# STM32_microcontroller_IOs.net
KiCad netlist of a schematic drawn in Altium Designer
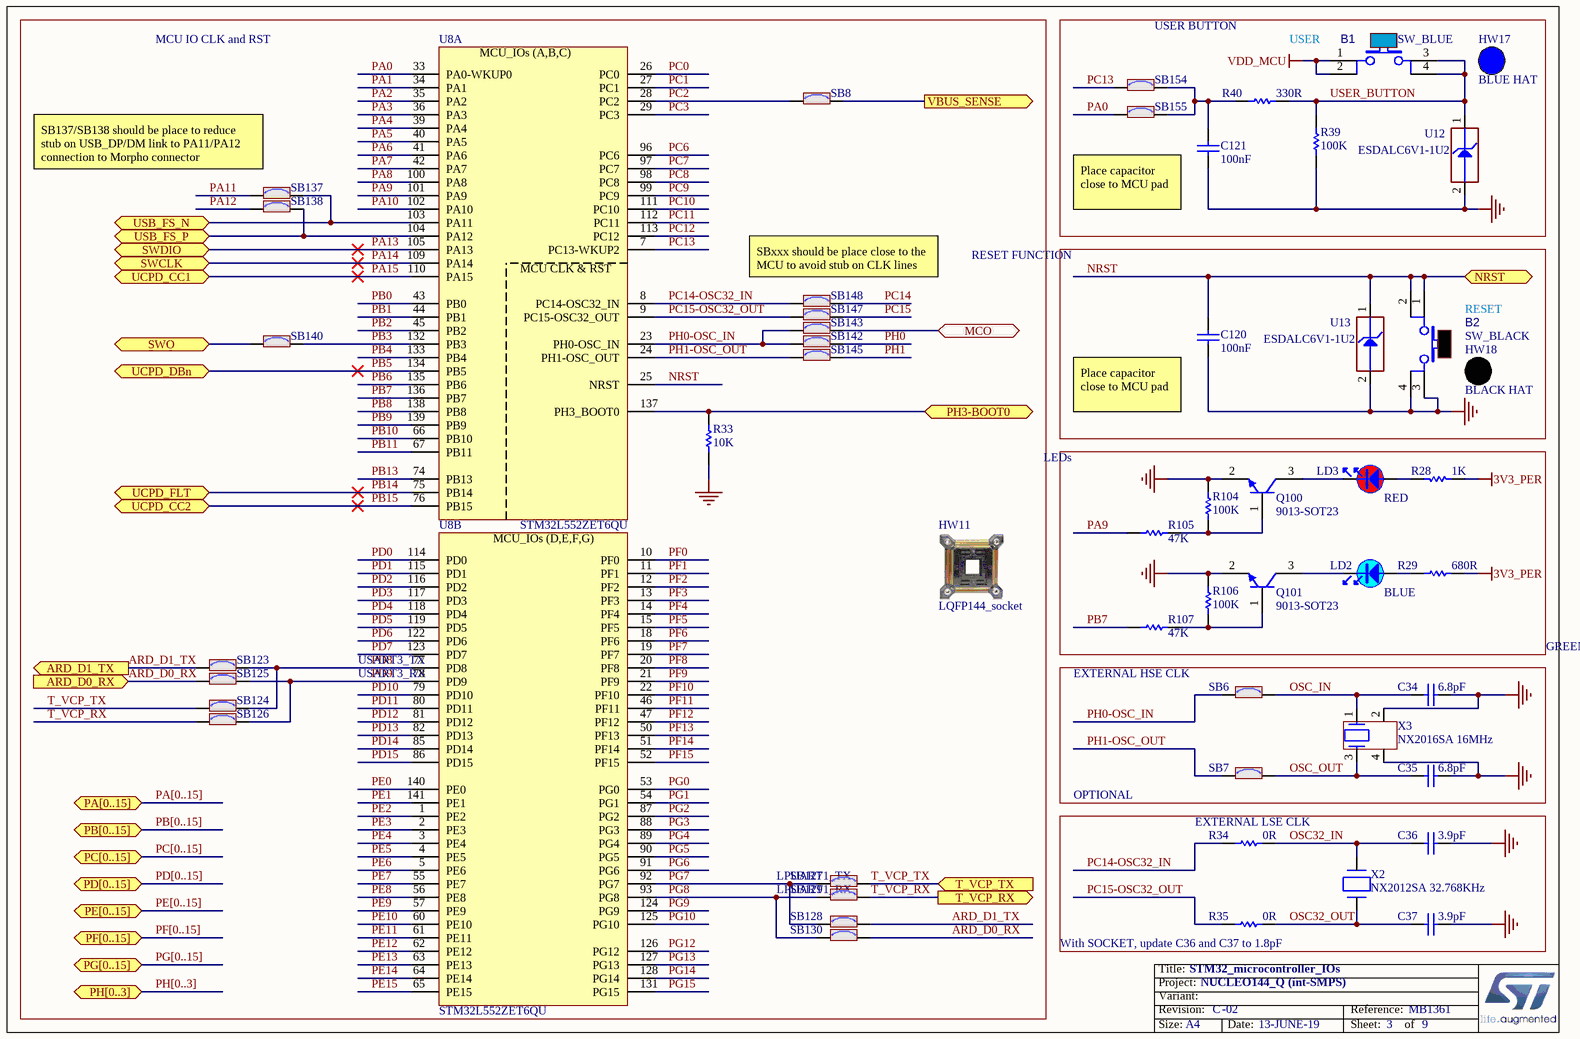
[diagram p0: STM32_microcontroller_IOs.SchDoc]

(export (version "E")
  (design (tool "Eeschema 10.0.6"))
  (components
    (comp (ref "B1")
      (value "SW_BLUE")
      (footprint "SWI_WEALTHMETAL_TD-0341_4P_BLUE")
      (description "Non-Open Push-Button 0.1A 24V BLUE")
      (fields
        (field (name "INTERNAL_PART_NUMBER") "MCD-00002")
        (field (name "MANUFACTURER_PART_NUMBER") "TD0341X-G01-BLU")
        (field (name "PROVIDED_BY") "Subcon")
      )
      (libsource (lib "MCD_PARTS_database") (part "SW-PUSH-CMS_BLUE"))
    )
    (comp (ref "B2")
      (value "SW_BLACK")
      (footprint "SWI_WEALTHMETAL_TD-0341_4P_BLACK")
      (description "Non-Open Push-Button 0.1A 24V BLACK")
      (fields
        (field (name "INTERNAL_PART_NUMBER") "MCD-00001")
        (field (name "MANUFACTURER_PART_NUMBER") "TD0341X-G01-BLA")
        (field (name "PROVIDED_BY") "Subcon")
      )
      (libsource (lib "MCD_PARTS_database") (part "SW-PUSH-CMS_BLACK"))
    )
    (comp (ref "C34")
      (value "6.8pF")
      (footprint "C0402")
      (description "Capacitor, MLCC, 6.8pF, 50V, NPO, +-0.25pF, 0402, T=0.5mm")
      (fields
        (field (name "INTERNAL_PART_NUMBER") "MCD-00674")
        (field (name "MANUFACTURER_PART_NUMBER") "CC0402CRNPO9BN6R8")
        (field (name "PROVIDED_BY") "Subcon")
      )
      (libsource (lib "MCD_PARTS_database") (part "Capacitor"))
    )
    (comp (ref "C35")
      (value "6.8pF")
      (footprint "C0402")
      (description "Capacitor, MLCC, 6.8pF, 50V, NPO, +-0.25pF, 0402, T=0.5mm")
      (fields
        (field (name "INTERNAL_PART_NUMBER") "MCD-00674")
        (field (name "MANUFACTURER_PART_NUMBER") "CC0402CRNPO9BN6R8")
        (field (name "PROVIDED_BY") "Subcon")
      )
      (libsource (lib "MCD_PARTS_database") (part "Capacitor"))
    )
    (comp (ref "C36")
      (value "3.9pF")
      (footprint "C0402")
      (description "Capacitor, MLCC, 3.9pF, 50V, NPO, +-0.25pF, 0402, T=0,5mm")
      (fields
        (field (name "INTERNAL_PART_NUMBER") "MCD-00556")
        (field (name "MANUFACTURER_PART_NUMBER") "CC0402CRNPO9BN3R9")
        (field (name "PROVIDED_BY") "SUBCO")
      )
      (libsource (lib "MCD_PARTS_database") (part "Capacitor"))
    )
    (comp (ref "C37")
      (value "3.9pF")
      (footprint "C0402")
      (description "Capacitor, MLCC, 3.9pF, 50V, NPO, +-0.25pF, 0402, T=0,5mm")
      (fields
        (field (name "INTERNAL_PART_NUMBER") "MCD-00556")
        (field (name "MANUFACTURER_PART_NUMBER") "CC0402CRNPO9BN3R9")
        (field (name "PROVIDED_BY") "SUBCO")
      )
      (libsource (lib "MCD_PARTS_database") (part "Capacitor"))
    )
    (comp (ref "C120")
      (value "100nF")
      (footprint "C0603")
      (description "Capacitor, MLCC, 100nF, 16V, X7R, 10%, 0603, T=0,8mm")
      (fields
        (field (name "INTERNAL_PART_NUMBER") "MCD-00211")
        (field (name "MANUFACTURER_PART_NUMBER") "CC0603KRX7R7BB104")
        (field (name "PROVIDED_BY") "Subcon")
      )
      (libsource (lib "MCD_PARTS_database") (part "Capacitor"))
    )
    (comp (ref "C121")
      (value "100nF")
      (footprint "C0603")
      (description "Capacitor, MLCC, 100nF, 16V, X7R, 10%, 0603, T=0,8mm")
      (fields
        (field (name "INTERNAL_PART_NUMBER") "MCD-00211")
        (field (name "MANUFACTURER_PART_NUMBER") "CC0603KRX7R7BB104")
        (field (name "PROVIDED_BY") "Subcon")
      )
      (libsource (lib "MCD_PARTS_database") (part "Capacitor"))
    )
    (comp (ref "HW11")
      (value "LQFP144_socket")
      (description "Yamaichi socket for LQFP144, with positioning pins.")
      (fields
        (field (name "INTERNAL_PART_NUMBER") "MCD-01015")
        (field (name "MANUFACTURER_PART_NUMBER") "IC149-144-145-B5")
        (field (name "PROVIDED_BY") "Subcon")
      )
      (libsource (lib "MCD_PARTS_database") (part "SOCKET_LQFP144"))
    )
    (comp (ref "HW17")
      (value "BLUE HAT")
      (description "Blue Hat for switch TD0341X-G01-BLU")
      (fields
        (field (name "INTERNAL_PART_NUMBER") "MCD-00634")
        (field (name "MANUFACTURER_PART_NUMBER") "988.16.09.3.00002_SH-517")
        (field (name "PROVIDED_BY") "Subcon")
      )
      (libsource (lib "MCD_PARTS_database") (part "BUTTON_HAT_BLUE"))
    )
    (comp (ref "HW18")
      (value "BLACK HAT")
      (description "Black Hat for switch TD0341X-G01-BLA")
      (fields
        (field (name "INTERNAL_PART_NUMBER") "MCD-00635")
        (field (name "MANUFACTURER_PART_NUMBER") "988.16.09.3.00003_SH-517")
        (field (name "PROVIDED_BY") "Subcon")
      )
      (libsource (lib "MCD_PARTS_database") (part "BUTTON_HAT_BLACK"))
    )
    (comp (ref "LD2")
      (value "BLUE")
      (footprint "LED_0603_VISHAY_VLMB1300-GS08_BLUE_1A2K_H0P8")
      (description "LED Blue, 0603 SMD, 3.3 V Forward Voltage")
      (fields
        (field (name "INTERNAL_PART_NUMBER") "MCD-00584")
        (field (name "MANUFACTURER_PART_NUMBER") "VLMB1300-GS08")
        (field (name "PROVIDED_BY") "Subcon")
      )
      (libsource (lib "MCD_PARTS_database") (part "LED_blue"))
    )
    (comp (ref "LD3")
      (value "RED")
      (footprint "LED_0603_RED_H0P4")
      (description "LED, Red, 0603")
      (fields
        (field (name "INTERNAL_PART_NUMBER") "MCD-00322")
        (field (name "MANUFACTURER_PART_NUMBER") "19-217/R6C-AL1M2VY/3T")
        (field (name "PROVIDED_BY") "Subcon")
      )
      (libsource (lib "MCD_PARTS_database") (part "LED_red"))
    )
    (comp (ref "Q100")
      (value "9013-SOT23")
      (footprint "NPN_SOT23")
      (description "NPN Bipolar Transistor")
      (fields
        (field (name "INTERNAL_PART_NUMBER") "MCD-00073")
        (field (name "MANUFACTURER_PART_NUMBER") "BSR14")
        (field (name "PROVIDED_BY") "Subcon")
      )
      (libsource (lib "MCD_PARTS_database") (part "9013-SOT23"))
    )
    (comp (ref "Q101")
      (value "9013-SOT23")
      (footprint "NPN_SOT23")
      (description "NPN Bipolar Transistor")
      (fields
        (field (name "INTERNAL_PART_NUMBER") "MCD-00073")
        (field (name "MANUFACTURER_PART_NUMBER") "BSR14")
        (field (name "PROVIDED_BY") "Subcon")
      )
      (libsource (lib "MCD_PARTS_database") (part "9013-SOT23"))
    )
    (comp (ref "R28")
      (value "1K")
      (footprint "R0603")
      (description "Resistor,1K,0603,1%,1/10W")
      (fields
        (field (name "INTERNAL_PART_NUMBER") "MCD-00070")
        (field (name "MANUFACTURER_PART_NUMBER") "RC0603FR-071KL")
        (field (name "PROVIDED_BY") "Subcon")
      )
      (libsource (lib "MCD_PARTS_database") (part "Resistor"))
    )
    (comp (ref "R29")
      (value "680R")
      (footprint "R0603")
      (description "Resistor,680R,0603,1%,1/10W")
      (fields
        (field (name "INTERNAL_PART_NUMBER") "MCD-00508")
        (field (name "MANUFACTURER_PART_NUMBER") "RC0603FR-07680RL")
        (field (name "PROVIDED_BY") "Subcon")
      )
      (libsource (lib "MCD_PARTS_database") (part "Resistor"))
    )
    (comp (ref "R33")
      (value "10K")
      (footprint "R0603")
      (description "Resistor,10K,0603,1%,1/10W")
      (fields
        (field (name "INTERNAL_PART_NUMBER") "MCD-00220")
        (field (name "MANUFACTURER_PART_NUMBER") "RC0603FR-0710KL")
        (field (name "PROVIDED_BY") "Subcon")
      )
      (libsource (lib "MCD_PARTS_database") (part "Resistor"))
    )
    (comp (ref "R34")
      (value "0R")
      (footprint "R0603")
      (description "Resistor,0R,0603,5%,1/10W")
      (fields
        (field (name "INTERNAL_PART_NUMBER") "MCD-00056")
        (field (name "MANUFACTURER_PART_NUMBER") "RC0603JR-070RL")
        (field (name "PROVIDED_BY") "subcon")
      )
      (libsource (lib "MCD_PARTS_database") (part "Resistor"))
    )
    (comp (ref "R35")
      (value "0R")
      (footprint "R0603")
      (description "Resistor,0R,0603,5%,1/10W")
      (fields
        (field (name "INTERNAL_PART_NUMBER") "MCD-00056")
        (field (name "MANUFACTURER_PART_NUMBER") "RC0603JR-070RL")
        (field (name "PROVIDED_BY") "subcon")
      )
      (libsource (lib "MCD_PARTS_database") (part "Resistor"))
    )
    (comp (ref "R39")
      (value "100K")
      (footprint "R0603")
      (description "Resistor,100K,0603,1%,1/10W")
      (fields
        (field (name "INTERNAL_PART_NUMBER") "MCD-00223")
        (field (name "MANUFACTURER_PART_NUMBER") "RC0603FR-07100KL")
        (field (name "PROVIDED_BY") "Subcon")
      )
      (libsource (lib "MCD_PARTS_database") (part "Resistor"))
    )
    (comp (ref "R40")
      (value "330R")
      (footprint "R0603")
      (description "Resistor,330R,0603,1%,1/10W")
      (fields
        (field (name "INTERNAL_PART_NUMBER") "MCD-00197")
        (field (name "MANUFACTURER_PART_NUMBER") "RC0603FR-07330RL")
        (field (name "PROVIDED_BY") "Subcon")
      )
      (libsource (lib "MCD_PARTS_database") (part "Resistor"))
    )
    (comp (ref "R104")
      (value "100K")
      (footprint "R0603")
      (description "Resistor,100K,0603,1%,1/10W")
      (fields
        (field (name "INTERNAL_PART_NUMBER") "MCD-00223")
        (field (name "MANUFACTURER_PART_NUMBER") "RC0603FR-07100KL")
        (field (name "PROVIDED_BY") "Subcon")
      )
      (libsource (lib "MCD_PARTS_database") (part "Resistor"))
    )
    (comp (ref "R105")
      (value "47K")
      (footprint "R0603")
      (description "Resistor,47K,0603,1%,1/10W")
      (fields
        (field (name "INTERNAL_PART_NUMBER") "MCD-00222")
        (field (name "MANUFACTURER_PART_NUMBER") "RC0603FR-0747KL")
        (field (name "PROVIDED_BY") "Subcon")
      )
      (libsource (lib "MCD_PARTS_database") (part "Resistor"))
    )
    (comp (ref "R106")
      (value "100K")
      (footprint "R0603")
      (description "Resistor,100K,0603,1%,1/10W")
      (fields
        (field (name "INTERNAL_PART_NUMBER") "MCD-00223")
        (field (name "MANUFACTURER_PART_NUMBER") "RC0603FR-07100KL")
        (field (name "PROVIDED_BY") "Subcon")
      )
      (libsource (lib "MCD_PARTS_database") (part "Resistor"))
    )
    (comp (ref "R107")
      (value "47K")
      (footprint "R0603")
      (description "Resistor,47K,0603,1%,1/10W")
      (fields
        (field (name "INTERNAL_PART_NUMBER") "MCD-00222")
        (field (name "MANUFACTURER_PART_NUMBER") "RC0603FR-0747KL")
        (field (name "PROVIDED_BY") "Subcon")
      )
      (libsource (lib "MCD_PARTS_database") (part "Resistor"))
    )
    (comp (ref "SB6")
      (value "~")
      (footprint "SOLDER-BRIDGE_R0603-0R")
      (description "Solder Bridge ON")
      (fields (field (name "INTERNAL_PART_NUMBER") "MCD-00071") (field (name "PROVIDED_BY") "Subcon"))
      (libsource (lib "MCD_PARTS_database") (part "SB_ON"))
    )
    (comp (ref "SB7")
      (value "~")
      (footprint "SOLDER-BRIDGE_R0603-0R")
      (description "Solder Bridge ON")
      (fields (field (name "INTERNAL_PART_NUMBER") "MCD-00071") (field (name "PROVIDED_BY") "Subcon"))
      (libsource (lib "MCD_PARTS_database") (part "SB_ON"))
    )
    (comp (ref "SB8")
      (value "~")
      (footprint "SOLDER-BRIDGE_R0603-0R")
      (description "Solder Bridge ON")
      (fields (field (name "INTERNAL_PART_NUMBER") "MCD-00071") (field (name "PROVIDED_BY") "Subcon"))
      (libsource (lib "MCD_PARTS_database") (part "SB_ON"))
    )
    (comp (ref "SB123")
      (value "~")
      (footprint "SOLDER-BRIDGE_R0603-0R")
      (description "Solder Bridge ON")
      (fields (field (name "INTERNAL_PART_NUMBER") "MCD-00071") (field (name "PROVIDED_BY") "Subcon"))
      (libsource (lib "") (part "SB_ON_1"))
    )
    (comp (ref "SB124")
      (value "~")
      (footprint "SOLDER-BRIDGE_R0603-0R")
      (description "Solder Bridge ON")
      (fields (field (name "INTERNAL_PART_NUMBER") "MCD-00071") (field (name "PROVIDED_BY") "Subcon"))
      (libsource (lib "") (part "SB_ON_1"))
    )
    (comp (ref "SB125")
      (value "~")
      (footprint "SOLDER-BRIDGE_R0603-0R")
      (description "Solder Bridge ON")
      (fields (field (name "INTERNAL_PART_NUMBER") "MCD-00071") (field (name "PROVIDED_BY") "Subcon"))
      (libsource (lib "") (part "SB_ON_1"))
    )
    (comp (ref "SB126")
      (value "~")
      (footprint "SOLDER-BRIDGE_R0603-0R")
      (description "Solder Bridge ON")
      (fields (field (name "INTERNAL_PART_NUMBER") "MCD-00071") (field (name "PROVIDED_BY") "Subcon"))
      (libsource (lib "") (part "SB_ON_1"))
    )
    (comp (ref "SB127")
      (value "~")
      (footprint "SOLDER-BRIDGE_R0603-0R")
      (description "Solder Bridge ON")
      (fields (field (name "INTERNAL_PART_NUMBER") "MCD-00071") (field (name "PROVIDED_BY") "Subcon"))
      (libsource (lib "") (part "SB_ON_1"))
    )
    (comp (ref "SB128")
      (value "~")
      (footprint "SOLDER-BRIDGE_R0603-0R")
      (description "Solder Bridge ON")
      (fields (field (name "INTERNAL_PART_NUMBER") "MCD-00071") (field (name "PROVIDED_BY") "Subcon"))
      (libsource (lib "") (part "SB_ON_1"))
    )
    (comp (ref "SB129")
      (value "~")
      (footprint "SOLDER-BRIDGE_R0603-0R")
      (description "Solder Bridge ON")
      (fields (field (name "INTERNAL_PART_NUMBER") "MCD-00071") (field (name "PROVIDED_BY") "Subcon"))
      (libsource (lib "") (part "SB_ON_1"))
    )
    (comp (ref "SB130")
      (value "~")
      (footprint "SOLDER-BRIDGE_R0603-0R")
      (description "Solder Bridge ON")
      (fields (field (name "INTERNAL_PART_NUMBER") "MCD-00071") (field (name "PROVIDED_BY") "Subcon"))
      (libsource (lib "") (part "SB_ON_1"))
    )
    (comp (ref "SB137")
      (value "~")
      (footprint "SOLDER-BRIDGE_R0603-0R")
      (description "Solder Bridge ON")
      (fields (field (name "INTERNAL_PART_NUMBER") "MCD-00071") (field (name "PROVIDED_BY") "Subcon"))
      (libsource (lib "MCD_PARTS_database") (part "SB_ON"))
    )
    (comp (ref "SB138")
      (value "~")
      (footprint "SOLDER-BRIDGE_R0603-0R")
      (description "Solder Bridge ON")
      (fields (field (name "INTERNAL_PART_NUMBER") "MCD-00071") (field (name "PROVIDED_BY") "Subcon"))
      (libsource (lib "MCD_PARTS_database") (part "SB_ON"))
    )
    (comp (ref "SB140")
      (value "~")
      (footprint "SOLDER-BRIDGE_R0603-0R")
      (description "Solder Bridge ON")
      (fields (field (name "INTERNAL_PART_NUMBER") "MCD-00071") (field (name "PROVIDED_BY") "Subcon"))
      (libsource (lib "MCD_PARTS_database") (part "SB_ON"))
    )
    (comp (ref "SB142")
      (value "~")
      (footprint "SOLDER-BRIDGE_R0603-0R")
      (description "Solder Bridge ON")
      (fields (field (name "INTERNAL_PART_NUMBER") "MCD-00071") (field (name "PROVIDED_BY") "Subcon"))
      (libsource (lib "MCD_PARTS_database") (part "SB_ON"))
    )
    (comp (ref "SB143")
      (value "~")
      (footprint "SOLDER-BRIDGE_R0603-0R")
      (description "Solder Bridge ON")
      (fields (field (name "INTERNAL_PART_NUMBER") "MCD-00071") (field (name "PROVIDED_BY") "Subcon"))
      (libsource (lib "MCD_PARTS_database") (part "SB_ON"))
    )
    (comp (ref "SB145")
      (value "~")
      (footprint "SOLDER-BRIDGE_R0603-0R")
      (description "Solder Bridge ON")
      (fields (field (name "INTERNAL_PART_NUMBER") "MCD-00071") (field (name "PROVIDED_BY") "Subcon"))
      (libsource (lib "MCD_PARTS_database") (part "SB_ON"))
    )
    (comp (ref "SB147")
      (value "~")
      (footprint "SOLDER-BRIDGE_R0603-0R")
      (description "Solder Bridge ON")
      (fields (field (name "INTERNAL_PART_NUMBER") "MCD-00071") (field (name "PROVIDED_BY") "Subcon"))
      (libsource (lib "MCD_PARTS_database") (part "SB_ON"))
    )
    (comp (ref "SB148")
      (value "~")
      (footprint "SOLDER-BRIDGE_R0603-0R")
      (description "Solder Bridge ON")
      (fields (field (name "INTERNAL_PART_NUMBER") "MCD-00071") (field (name "PROVIDED_BY") "Subcon"))
      (libsource (lib "MCD_PARTS_database") (part "SB_ON"))
    )
    (comp (ref "SB154")
      (value "~")
      (footprint "SOLDER-BRIDGE_R0603-0R")
      (description "Solder Bridge ON")
      (fields (field (name "INTERNAL_PART_NUMBER") "MCD-00071") (field (name "PROVIDED_BY") "Subcon"))
      (libsource (lib "") (part "SB_ON_1"))
    )
    (comp (ref "SB155")
      (value "~")
      (footprint "SOLDER-BRIDGE_R0603-0R")
      (description "Solder Bridge ON")
      (fields (field (name "INTERNAL_PART_NUMBER") "MCD-00071") (field (name "PROVIDED_BY") "Subcon"))
      (libsource (lib "") (part "SB_ON_1"))
    )
    (comp (ref "U8")
      (value "STM32L552ZET6QU")
      (footprint "ICC_LQFP144_20X20_P050")
      (description "STM32L552ZET6Q MCU,LQFP144 20x20, 0.5, no AES, Q for Int SMPS")
      (fields
        (field (name "INTERNAL_PART_NUMBER") "MCD-01055")
        (field (name "MANUFACTURER") "STMICROELECTRONICS")
        (field (name "PROVIDED_BY") "SUBCO with ST control")
      )
      (libsource (lib "MCD_PARTS_database") (part "STM32L552ZET6QU"))
    )
    (comp (ref "U12")
      (value "ESDALC6V1-1U2")
      (footprint "ESD_ST0201")
      (description "ESD protection 6V1")
      (fields
        (field (name "INTERNAL_PART_NUMBER") "MCD-00170")
        (field (name "MANUFACTURER") "STMICROELECTRONICS")
        (field (name "PROVIDED_BY") "Subcon")
      )
      (libsource (lib "MCD_PARTS_database") (part "ESD-TRANSIL"))
    )
    (comp (ref "U13")
      (value "ESDALC6V1-1U2")
      (footprint "ESD_ST0201")
      (description "ESD protection 6V1")
      (fields
        (field (name "INTERNAL_PART_NUMBER") "MCD-00170")
        (field (name "MANUFACTURER") "STMICROELECTRONICS")
        (field (name "PROVIDED_BY") "Subcon")
      )
      (libsource (lib "MCD_PARTS_database") (part "ESD-TRANSIL"))
    )
    (comp (ref "X2")
      (value "NX2012SA 32.768KHz")
      (footprint "CRY_NX2012SA_2P")
      (description "Crystal 32.768kHz, 6pF, -+20PPM, R=80K, SMD")
      (fields
        (field (name "INTERNAL_PART_NUMBER") "MCD-01479")
        (field (name "MANUFACTURER_PART_NUMBER") "NX2012SA 32.768KHz EXS00A-MU00527")
        (field (name "PROVIDED_BY") "SUBCO")
      )
      (libsource (lib "MCD_PARTS_database") (part "XTAL_2_PINS"))
    )
    (comp (ref "X3")
      (value "NX2016SA 16MHz")
      (footprint "CRY_NX2016SA_4P")
      (description "Crystal 16 MHz, 8pF, -+20 PPM, R=200Ω, SMD")
      (fields
        (field (name "INTERNAL_PART_NUMBER") "MCD-01476")
        (field (name "MANUFACTURER_PART_NUMBER") "NX2016SA 16 MHz EXS00A-CS07826")
      )
      (libsource (lib "MCD_PARTS_database") (part "XTAL_4_PINS"))
    )
  )
  (nets
    (net (code "7") (name "/ARD_D0_RX") (class "Default")
      (node (ref "SB125") (pin "2") (pinfunction "2_2") (pintype "passive"))
      (node (ref "SB130") (pin "1") (pinfunction "1_1") (pintype "passive"))
    )
    (net (code "8") (name "/ARD_D1_TX") (class "Default")
      (node (ref "SB123") (pin "2") (pinfunction "2_2") (pintype "passive"))
      (node (ref "SB128") (pin "1") (pinfunction "1_1") (pintype "passive"))
    )
    (net (code "9") (name "/MCO") (class "Default")
      (node (ref "SB143") (pin "2") (pinfunction "2_2") (pintype "passive"))
    )
    (net (code "10") (name "/NRST") (class "Default")
      (node (ref "B2") (pin "1") (pinfunction "1_1") (pintype "passive"))
      (node (ref "B2") (pin "2") (pinfunction "2_2") (pintype "passive"))
      (node (ref "C120") (pin "2") (pinfunction "2_2") (pintype "passive"))
      (node (ref "U13") (pin "1") (pinfunction "IO1_1") (pintype "passive"))
      (node (ref "U8") (pin "25") (pinfunction "NRST_25") (pintype "passive"))
    )
    (net (code "11") (name "/OSC32_IN") (class "Default")
      (node (ref "C36") (pin "1") (pinfunction "1_1") (pintype "passive"))
      (node (ref "R34") (pin "2") (pinfunction "2_2") (pintype "passive"))
      (node (ref "X2") (pin "2") (pinfunction "X2_2") (pintype "passive"))
    )
    (net (code "12") (name "/OSC32_OUT") (class "Default")
      (node (ref "C37") (pin "1") (pinfunction "1_1") (pintype "passive"))
      (node (ref "R35") (pin "2") (pinfunction "2_2") (pintype "passive"))
      (node (ref "X2") (pin "1") (pinfunction "X1_1") (pintype "passive"))
    )
    (net (code "13") (name "/OSC_IN") (class "Default")
      (node (ref "C34") (pin "1") (pinfunction "1_1") (pintype "passive"))
      (node (ref "SB6") (pin "2") (pinfunction "2_2") (pintype "passive"))
      (node (ref "X3") (pin "1") (pinfunction "1_1") (pintype "passive"))
    )
    (net (code "14") (name "/OSC_OUT") (class "Default")
      (node (ref "C35") (pin "1") (pinfunction "1_1") (pintype "passive"))
      (node (ref "SB7") (pin "2") (pinfunction "2_2") (pintype "passive"))
      (node (ref "X3") (pin "3") (pinfunction "3_3") (pintype "passive"))
    )
    (net (code "15") (name "/PA0") (class "Default")
      (node (ref "SB155") (pin "2") (pinfunction "2_2") (pintype "passive"))
      (node (ref "U8") (pin "33") (pinfunction "PA0-WKUP0_33") (pintype "passive"))
    )
    (net (code "16") (name "/PA1") (class "Default")
      (node (ref "U8") (pin "34") (pinfunction "PA1_34") (pintype "passive"))
    )
    (net (code "17") (name "/PA2") (class "Default")
      (node (ref "U8") (pin "35") (pinfunction "PA2_35") (pintype "passive"))
    )
    (net (code "18") (name "/PA3") (class "Default")
      (node (ref "U8") (pin "36") (pinfunction "PA3_36") (pintype "passive"))
    )
    (net (code "19") (name "/PA4") (class "Default")
      (node (ref "U8") (pin "39") (pinfunction "PA4_39") (pintype "passive"))
    )
    (net (code "20") (name "/PA5") (class "Default")
      (node (ref "U8") (pin "40") (pinfunction "PA5_40") (pintype "passive"))
    )
    (net (code "21") (name "/PA6") (class "Default")
      (node (ref "U8") (pin "41") (pinfunction "PA6_41") (pintype "passive"))
    )
    (net (code "22") (name "/PA7") (class "Default")
      (node (ref "U8") (pin "42") (pinfunction "PA7_42") (pintype "passive"))
    )
    (net (code "23") (name "/PA8") (class "Default")
      (node (ref "U8") (pin "100") (pinfunction "PA8_100") (pintype "passive"))
    )
    (net (code "24") (name "/PA9") (class "Default")
      (node (ref "R105") (pin "1") (pinfunction "1_1") (pintype "passive"))
      (node (ref "U8") (pin "101") (pinfunction "PA9_101") (pintype "passive"))
    )
    (net (code "25") (name "/PA10") (class "Default")
      (node (ref "U8") (pin "102") (pinfunction "PA10_102") (pintype "passive"))
    )
    (net (code "26") (name "/PA11") (class "Default")
      (node (ref "SB137") (pin "1") (pinfunction "1_1") (pintype "passive"))
    )
    (net (code "27") (name "/PA12") (class "Default")
      (node (ref "SB138") (pin "1") (pinfunction "1_1") (pintype "passive"))
    )
    (net (code "28") (name "/PA13") (class "Default")
      (node (ref "U8") (pin "105") (pinfunction "PA13_105") (pintype "passive"))
    )
    (net (code "29") (name "/PA14") (class "Default")
      (node (ref "U8") (pin "109") (pinfunction "PA14_109") (pintype "passive"))
    )
    (net (code "30") (name "/PA15") (class "Default")
      (node (ref "U8") (pin "110") (pinfunction "PA15_110") (pintype "passive"))
    )
    (net (code "32") (name "/PB0") (class "Default")
      (node (ref "U8") (pin "43") (pinfunction "PB0_43") (pintype "passive"))
    )
    (net (code "33") (name "/PB1") (class "Default")
      (node (ref "U8") (pin "44") (pinfunction "PB1_44") (pintype "passive"))
    )
    (net (code "34") (name "/PB2") (class "Default")
      (node (ref "U8") (pin "45") (pinfunction "PB2_45") (pintype "passive"))
    )
    (net (code "35") (name "/PB3") (class "Default")
      (node (ref "SB140") (pin "2") (pinfunction "2_2") (pintype "passive"))
      (node (ref "U8") (pin "132") (pinfunction "PB3_132") (pintype "passive"))
    )
    (net (code "36") (name "/PB4") (class "Default")
      (node (ref "U8") (pin "133") (pinfunction "PB4_133") (pintype "passive"))
    )
    (net (code "37") (name "/PB5") (class "Default")
      (node (ref "U8") (pin "134") (pinfunction "PB5_134") (pintype "passive"))
    )
    (net (code "38") (name "/PB6") (class "Default")
      (node (ref "U8") (pin "135") (pinfunction "PB6_135") (pintype "passive"))
    )
    (net (code "39") (name "/PB7") (class "Default")
      (node (ref "R107") (pin "1") (pinfunction "1_1") (pintype "passive"))
      (node (ref "U8") (pin "136") (pinfunction "PB7_136") (pintype "passive"))
    )
    (net (code "40") (name "/PB8") (class "Default")
      (node (ref "U8") (pin "138") (pinfunction "PB8_138") (pintype "passive"))
    )
    (net (code "41") (name "/PB9") (class "Default")
      (node (ref "U8") (pin "139") (pinfunction "PB9_139") (pintype "passive"))
    )
    (net (code "42") (name "/PB10") (class "Default")
      (node (ref "U8") (pin "66") (pinfunction "PB10_66") (pintype "passive"))
    )
    (net (code "43") (name "/PB11") (class "Default")
      (node (ref "U8") (pin "67") (pinfunction "PB11_67") (pintype "passive"))
    )
    (net (code "44") (name "/PB13") (class "Default")
      (node (ref "U8") (pin "74") (pinfunction "PB13_74") (pintype "passive"))
    )
    (net (code "45") (name "/PB14") (class "Default")
      (node (ref "U8") (pin "75") (pinfunction "PB14_75") (pintype "passive"))
    )
    (net (code "46") (name "/PB15") (class "Default")
      (node (ref "U8") (pin "76") (pinfunction "PB15_76") (pintype "passive"))
    )
    (net (code "48") (name "/PC0") (class "Default")
      (node (ref "U8") (pin "26") (pinfunction "PC0_26") (pintype "passive"))
    )
    (net (code "49") (name "/PC1") (class "Default")
      (node (ref "U8") (pin "27") (pinfunction "PC1_27") (pintype "passive"))
    )
    (net (code "50") (name "/PC2") (class "Default")
      (node (ref "SB8") (pin "1") (pinfunction "1_1") (pintype "passive"))
      (node (ref "U8") (pin "28") (pinfunction "PC2_28") (pintype "passive"))
    )
    (net (code "51") (name "/PC3") (class "Default")
      (node (ref "U8") (pin "29") (pinfunction "PC3_29") (pintype "passive"))
    )
    (net (code "52") (name "/PC6") (class "Default")
      (node (ref "U8") (pin "96") (pinfunction "PC6_96") (pintype "passive"))
    )
    (net (code "53") (name "/PC7") (class "Default")
      (node (ref "U8") (pin "97") (pinfunction "PC7_97") (pintype "passive"))
    )
    (net (code "54") (name "/PC8") (class "Default")
      (node (ref "U8") (pin "98") (pinfunction "PC8_98") (pintype "passive"))
    )
    (net (code "55") (name "/PC9") (class "Default")
      (node (ref "U8") (pin "99") (pinfunction "PC9_99") (pintype "passive"))
    )
    (net (code "56") (name "/PC10") (class "Default")
      (node (ref "U8") (pin "111") (pinfunction "PC10_111") (pintype "passive"))
    )
    (net (code "57") (name "/PC11") (class "Default")
      (node (ref "U8") (pin "112") (pinfunction "PC11_112") (pintype "passive"))
    )
    (net (code "58") (name "/PC12") (class "Default")
      (node (ref "U8") (pin "113") (pinfunction "PC12_113") (pintype "passive"))
    )
    (net (code "59") (name "/PC13") (class "Default")
      (node (ref "SB154") (pin "2") (pinfunction "2_2") (pintype "passive"))
      (node (ref "U8") (pin "7") (pinfunction "PC13-WKUP2_7") (pintype "passive"))
    )
    (net (code "60") (name "/PC14") (class "Default")
      (node (ref "SB148") (pin "2") (pinfunction "2_2") (pintype "passive"))
    )
    (net (code "61") (name "/PC14-OSC32_IN") (class "Default")
      (node (ref "R34") (pin "1") (pinfunction "1_1") (pintype "passive"))
      (node (ref "SB148") (pin "1") (pinfunction "1_1") (pintype "passive"))
      (node (ref "U8") (pin "8") (pinfunction "PC14-OSC32_IN_8") (pintype "passive"))
    )
    (net (code "62") (name "/PC15") (class "Default")
      (node (ref "SB147") (pin "2") (pinfunction "2_2") (pintype "passive"))
    )
    (net (code "63") (name "/PC15-OSC32_OUT") (class "Default")
      (node (ref "R35") (pin "1") (pinfunction "1_1") (pintype "passive"))
      (node (ref "SB147") (pin "1") (pinfunction "1_1") (pintype "passive"))
      (node (ref "U8") (pin "9") (pinfunction "PC15-OSC32_OUT_9") (pintype "passive"))
    )
    (net (code "65") (name "/PD0") (class "Default")
      (node (ref "U8") (pin "114") (pinfunction "PD0_114") (pintype "passive"))
    )
    (net (code "66") (name "/PD1") (class "Default")
      (node (ref "U8") (pin "115") (pinfunction "PD1_115") (pintype "passive"))
    )
    (net (code "67") (name "/PD2") (class "Default")
      (node (ref "U8") (pin "116") (pinfunction "PD2_116") (pintype "passive"))
    )
    (net (code "68") (name "/PD3") (class "Default")
      (node (ref "U8") (pin "117") (pinfunction "PD3_117") (pintype "passive"))
    )
    (net (code "69") (name "/PD4") (class "Default")
      (node (ref "U8") (pin "118") (pinfunction "PD4_118") (pintype "passive"))
    )
    (net (code "70") (name "/PD5") (class "Default")
      (node (ref "U8") (pin "119") (pinfunction "PD5_119") (pintype "passive"))
    )
    (net (code "71") (name "/PD6") (class "Default")
      (node (ref "U8") (pin "122") (pinfunction "PD6_122") (pintype "passive"))
    )
    (net (code "72") (name "/PD7") (class "Default")
      (node (ref "U8") (pin "123") (pinfunction "PD7_123") (pintype "passive"))
    )
    (net (code "73") (name "/PD8") (class "Default")
      (node (ref "SB123") (pin "1") (pinfunction "1_1") (pintype "passive"))
      (node (ref "SB124") (pin "1") (pinfunction "1_1") (pintype "passive"))
      (node (ref "U8") (pin "77") (pinfunction "PD8_77") (pintype "passive"))
    )
    (net (code "74") (name "/PD9") (class "Default")
      (node (ref "SB125") (pin "1") (pinfunction "1_1") (pintype "passive"))
      (node (ref "SB126") (pin "1") (pinfunction "1_1") (pintype "passive"))
      (node (ref "U8") (pin "78") (pinfunction "PD9_78") (pintype "passive"))
    )
    (net (code "75") (name "/PD10") (class "Default")
      (node (ref "U8") (pin "79") (pinfunction "PD10_79") (pintype "passive"))
    )
    (net (code "76") (name "/PD11") (class "Default")
      (node (ref "U8") (pin "80") (pinfunction "PD11_80") (pintype "passive"))
    )
    (net (code "77") (name "/PD12") (class "Default")
      (node (ref "U8") (pin "81") (pinfunction "PD12_81") (pintype "passive"))
    )
    (net (code "78") (name "/PD13") (class "Default")
      (node (ref "U8") (pin "82") (pinfunction "PD13_82") (pintype "passive"))
    )
    (net (code "79") (name "/PD14") (class "Default")
      (node (ref "U8") (pin "85") (pinfunction "PD14_85") (pintype "passive"))
    )
    (net (code "80") (name "/PD15") (class "Default")
      (node (ref "U8") (pin "86") (pinfunction "PD15_86") (pintype "passive"))
    )
    (net (code "82") (name "/PE0") (class "Default")
      (node (ref "U8") (pin "140") (pinfunction "PE0_140") (pintype "passive"))
    )
    (net (code "83") (name "/PE1") (class "Default")
      (node (ref "U8") (pin "141") (pinfunction "PE1_141") (pintype "passive"))
    )
    (net (code "84") (name "/PE2") (class "Default")
      (node (ref "U8") (pin "1") (pinfunction "PE2_1") (pintype "passive"))
    )
    (net (code "85") (name "/PE3") (class "Default")
      (node (ref "U8") (pin "2") (pinfunction "PE3_2") (pintype "passive"))
    )
    (net (code "86") (name "/PE4") (class "Default")
      (node (ref "U8") (pin "3") (pinfunction "PE4_3") (pintype "passive"))
    )
    (net (code "87") (name "/PE5") (class "Default")
      (node (ref "U8") (pin "4") (pinfunction "PE5_4") (pintype "passive"))
    )
    (net (code "88") (name "/PE6") (class "Default")
      (node (ref "U8") (pin "5") (pinfunction "PE6_5") (pintype "passive"))
    )
    (net (code "89") (name "/PE7") (class "Default")
      (node (ref "U8") (pin "55") (pinfunction "PE7_55") (pintype "passive"))
    )
    (net (code "90") (name "/PE8") (class "Default")
      (node (ref "U8") (pin "56") (pinfunction "PE8_56") (pintype "passive"))
    )
    (net (code "91") (name "/PE9") (class "Default")
      (node (ref "U8") (pin "57") (pinfunction "PE9_57") (pintype "passive"))
    )
    (net (code "92") (name "/PE10") (class "Default")
      (node (ref "U8") (pin "60") (pinfunction "PE10_60") (pintype "passive"))
    )
    (net (code "93") (name "/PE11") (class "Default")
      (node (ref "U8") (pin "61") (pinfunction "PE11_61") (pintype "passive"))
    )
    (net (code "94") (name "/PE12") (class "Default")
      (node (ref "U8") (pin "62") (pinfunction "PE12_62") (pintype "passive"))
    )
    (net (code "95") (name "/PE13") (class "Default")
      (node (ref "U8") (pin "63") (pinfunction "PE13_63") (pintype "passive"))
    )
    (net (code "96") (name "/PE14") (class "Default")
      (node (ref "U8") (pin "64") (pinfunction "PE14_64") (pintype "passive"))
    )
    (net (code "97") (name "/PE15") (class "Default")
      (node (ref "U8") (pin "65") (pinfunction "PE15_65") (pintype "passive"))
    )
    (net (code "99") (name "/PF0") (class "Default")
      (node (ref "U8") (pin "10") (pinfunction "PF0_10") (pintype "passive"))
    )
    (net (code "100") (name "/PF1") (class "Default")
      (node (ref "U8") (pin "11") (pinfunction "PF1_11") (pintype "passive"))
    )
    (net (code "101") (name "/PF2") (class "Default")
      (node (ref "U8") (pin "12") (pinfunction "PF2_12") (pintype "passive"))
    )
    (net (code "102") (name "/PF3") (class "Default")
      (node (ref "U8") (pin "13") (pinfunction "PF3_13") (pintype "passive"))
    )
    (net (code "103") (name "/PF4") (class "Default")
      (node (ref "U8") (pin "14") (pinfunction "PF4_14") (pintype "passive"))
    )
    (net (code "104") (name "/PF5") (class "Default")
      (node (ref "U8") (pin "15") (pinfunction "PF5_15") (pintype "passive"))
    )
    (net (code "105") (name "/PF6") (class "Default")
      (node (ref "U8") (pin "18") (pinfunction "PF6_18") (pintype "passive"))
    )
    (net (code "106") (name "/PF7") (class "Default")
      (node (ref "U8") (pin "19") (pinfunction "PF7_19") (pintype "passive"))
    )
    (net (code "107") (name "/PF8") (class "Default")
      (node (ref "U8") (pin "20") (pinfunction "PF8_20") (pintype "passive"))
    )
    (net (code "108") (name "/PF9") (class "Default")
      (node (ref "U8") (pin "21") (pinfunction "PF9_21") (pintype "passive"))
    )
    (net (code "109") (name "/PF10") (class "Default")
      (node (ref "U8") (pin "22") (pinfunction "PF10_22") (pintype "passive"))
    )
    (net (code "110") (name "/PF11") (class "Default")
      (node (ref "U8") (pin "46") (pinfunction "PF11_46") (pintype "passive"))
    )
    (net (code "111") (name "/PF12") (class "Default")
      (node (ref "U8") (pin "47") (pinfunction "PF12_47") (pintype "passive"))
    )
    (net (code "112") (name "/PF13") (class "Default")
      (node (ref "U8") (pin "50") (pinfunction "PF13_50") (pintype "passive"))
    )
    (net (code "113") (name "/PF14") (class "Default")
      (node (ref "U8") (pin "51") (pinfunction "PF14_51") (pintype "passive"))
    )
    (net (code "114") (name "/PF15") (class "Default")
      (node (ref "U8") (pin "52") (pinfunction "PF15_52") (pintype "passive"))
    )
    (net (code "116") (name "/PG0") (class "Default")
      (node (ref "U8") (pin "53") (pinfunction "PG0_53") (pintype "passive"))
    )
    (net (code "117") (name "/PG1") (class "Default")
      (node (ref "U8") (pin "54") (pinfunction "PG1_54") (pintype "passive"))
    )
    (net (code "118") (name "/PG2") (class "Default")
      (node (ref "U8") (pin "87") (pinfunction "PG2_87") (pintype "passive"))
    )
    (net (code "119") (name "/PG3") (class "Default")
      (node (ref "U8") (pin "88") (pinfunction "PG3_88") (pintype "passive"))
    )
    (net (code "120") (name "/PG4") (class "Default")
      (node (ref "U8") (pin "89") (pinfunction "PG4_89") (pintype "passive"))
    )
    (net (code "121") (name "/PG5") (class "Default")
      (node (ref "U8") (pin "90") (pinfunction "PG5_90") (pintype "passive"))
    )
    (net (code "122") (name "/PG6") (class "Default")
      (node (ref "U8") (pin "91") (pinfunction "PG6_91") (pintype "passive"))
    )
    (net (code "123") (name "/PG7") (class "Default")
      (node (ref "SB127") (pin "2") (pinfunction "2_2") (pintype "passive"))
      (node (ref "SB128") (pin "2") (pinfunction "2_2") (pintype "passive"))
      (node (ref "U8") (pin "92") (pinfunction "PG7_92") (pintype "passive"))
    )
    (net (code "124") (name "/PG8") (class "Default")
      (node (ref "SB129") (pin "2") (pinfunction "2_2") (pintype "passive"))
      (node (ref "SB130") (pin "2") (pinfunction "2_2") (pintype "passive"))
      (node (ref "U8") (pin "93") (pinfunction "PG8_93") (pintype "passive"))
    )
    (net (code "125") (name "/PG9") (class "Default")
      (node (ref "U8") (pin "124") (pinfunction "PG9_124") (pintype "passive"))
    )
    (net (code "126") (name "/PG10") (class "Default")
      (node (ref "U8") (pin "125") (pinfunction "PG10_125") (pintype "passive"))
    )
    (net (code "127") (name "/PG12") (class "Default")
      (node (ref "U8") (pin "126") (pinfunction "PG12_126") (pintype "passive"))
    )
    (net (code "128") (name "/PG13") (class "Default")
      (node (ref "U8") (pin "127") (pinfunction "PG13_127") (pintype "passive"))
    )
    (net (code "129") (name "/PG14") (class "Default")
      (node (ref "U8") (pin "128") (pinfunction "PG14_128") (pintype "passive"))
    )
    (net (code "130") (name "/PG15") (class "Default")
      (node (ref "U8") (pin "131") (pinfunction "PG15_131") (pintype "passive"))
    )
    (net (code "132") (name "/PH0") (class "Default")
      (node (ref "SB142") (pin "2") (pinfunction "2_2") (pintype "passive"))
    )
    (net (code "133") (name "/PH0-OSC_IN") (class "Default")
      (node (ref "SB142") (pin "1") (pinfunction "1_1") (pintype "passive"))
      (node (ref "SB143") (pin "1") (pinfunction "1_1") (pintype "passive"))
      (node (ref "SB6") (pin "1") (pinfunction "1_1") (pintype "passive"))
      (node (ref "U8") (pin "23") (pinfunction "PH0-OSC_IN_23") (pintype "passive"))
    )
    (net (code "134") (name "/PH1") (class "Default")
      (node (ref "SB145") (pin "2") (pinfunction "2_2") (pintype "passive"))
    )
    (net (code "135") (name "/PH1-OSC_OUT") (class "Default")
      (node (ref "SB145") (pin "1") (pinfunction "1_1") (pintype "passive"))
      (node (ref "SB7") (pin "1") (pinfunction "1_1") (pintype "passive"))
      (node (ref "U8") (pin "24") (pinfunction "PH1-OSC_OUT_24") (pintype "passive"))
    )
    (net (code "136") (name "/PH3-BOOT0") (class "Default")
      (node (ref "R33") (pin "1") (pinfunction "1_1") (pintype "passive"))
      (node (ref "U8") (pin "137") (pinfunction "PH3_BOOT0_137") (pintype "passive"))
    )
    (net (code "138") (name "/SWO") (class "Default")
      (node (ref "SB140") (pin "1") (pinfunction "1_1") (pintype "passive"))
    )
    (net (code "139") (name "/T_VCP_RX") (class "Default")
      (node (ref "SB126") (pin "2") (pinfunction "2_2") (pintype "passive"))
      (node (ref "SB129") (pin "1") (pinfunction "1_1") (pintype "passive"))
    )
    (net (code "140") (name "/T_VCP_TX") (class "Default")
      (node (ref "SB124") (pin "2") (pinfunction "2_2") (pintype "passive"))
      (node (ref "SB127") (pin "1") (pinfunction "1_1") (pintype "passive"))
    )
    (net (code "141") (name "/USB_FS_N") (class "Default")
      (node (ref "SB137") (pin "2") (pinfunction "2_2") (pintype "passive"))
      (node (ref "U8") (pin "103") (pinfunction "PA11_103") (pintype "passive"))
    )
    (net (code "142") (name "/USB_FS_P") (class "Default")
      (node (ref "SB138") (pin "2") (pinfunction "2_2") (pintype "passive"))
      (node (ref "U8") (pin "104") (pinfunction "PA12_104") (pintype "passive"))
    )
    (net (code "143") (name "/USER_BUTTON") (class "Default")
      (node (ref "B1") (pin "3") (pinfunction "3_3") (pintype "passive"))
      (node (ref "B1") (pin "4") (pinfunction "4_4") (pintype "passive"))
      (node (ref "R39") (pin "2") (pinfunction "2_2") (pintype "passive"))
      (node (ref "R40") (pin "2") (pinfunction "2_2") (pintype "passive"))
      (node (ref "U12") (pin "1") (pinfunction "IO1_1") (pintype "passive"))
    )
    (net (code "144") (name "/VBUS_SENSE") (class "Default")
      (node (ref "SB8") (pin "2") (pinfunction "2_2") (pintype "passive"))
    )
    (net (code "145") (name "3V3_PER") (class "Default")
      (node (ref "R28") (pin "1") (pinfunction "1_1") (pintype "passive"))
      (node (ref "R29") (pin "1") (pinfunction "1_1") (pintype "passive"))
    )
    (net (code "146") (name "GND") (class "Default")
      (node (ref "B2") (pin "3") (pinfunction "3_3") (pintype "passive"))
      (node (ref "B2") (pin "4") (pinfunction "4_4") (pintype "passive"))
      (node (ref "C120") (pin "1") (pinfunction "1_1") (pintype "passive"))
      (node (ref "C121") (pin "1") (pinfunction "1_1") (pintype "passive"))
      (node (ref "C34") (pin "2") (pinfunction "2_2") (pintype "passive"))
      (node (ref "C35") (pin "2") (pinfunction "2_2") (pintype "passive"))
      (node (ref "C36") (pin "2") (pinfunction "2_2") (pintype "passive"))
      (node (ref "C37") (pin "2") (pinfunction "2_2") (pintype "passive"))
      (node (ref "Q100") (pin "2") (pinfunction "E_2") (pintype "passive"))
      (node (ref "Q101") (pin "2") (pinfunction "E_2") (pintype "passive"))
      (node (ref "R104") (pin "1") (pinfunction "1_1") (pintype "passive"))
      (node (ref "R106") (pin "1") (pinfunction "1_1") (pintype "passive"))
      (node (ref "R33") (pin "2") (pinfunction "2_2") (pintype "passive"))
      (node (ref "R39") (pin "1") (pinfunction "1_1") (pintype "passive"))
      (node (ref "U12") (pin "2") (pinfunction "GND_2") (pintype "passive"))
      (node (ref "U13") (pin "2") (pinfunction "GND_2") (pintype "passive"))
      (node (ref "X3") (pin "2") (pinfunction "2_2") (pintype "passive"))
      (node (ref "X3") (pin "4") (pinfunction "4_4") (pintype "passive"))
    )
    (net (code "147") (name "Net-(C121-Pad2)") (class "Default")
      (node (ref "C121") (pin "2") (pinfunction "2_2") (pintype "passive"))
      (node (ref "R40") (pin "1") (pinfunction "1_1") (pintype "passive"))
      (node (ref "SB154") (pin "1") (pinfunction "1_1") (pintype "passive"))
      (node (ref "SB155") (pin "1") (pinfunction "1_1") (pintype "passive"))
    )
    (net (code "148") (name "Net-(LD2-Pad1)") (class "Default")
      (node (ref "LD2") (pin "1") (pintype "passive"))
      (node (ref "R29") (pin "2") (pinfunction "2_2") (pintype "passive"))
    )
    (net (code "149") (name "Net-(LD3-Pad1)") (class "Default")
      (node (ref "LD3") (pin "1") (pintype "passive"))
      (node (ref "R28") (pin "2") (pinfunction "2_2") (pintype "passive"))
    )
    (net (code "150") (name "Net-(Q100-B)") (class "Default")
      (node (ref "Q100") (pin "1") (pinfunction "B_1") (pintype "passive"))
      (node (ref "R104") (pin "2") (pinfunction "2_2") (pintype "passive"))
      (node (ref "R105") (pin "2") (pinfunction "2_2") (pintype "passive"))
    )
    (net (code "151") (name "Net-(Q100-C)") (class "Default")
      (node (ref "LD3") (pin "2") (pintype "passive"))
      (node (ref "Q100") (pin "3") (pinfunction "C_3") (pintype "passive"))
    )
    (net (code "152") (name "Net-(Q101-B)") (class "Default")
      (node (ref "Q101") (pin "1") (pinfunction "B_1") (pintype "passive"))
      (node (ref "R106") (pin "2") (pinfunction "2_2") (pintype "passive"))
      (node (ref "R107") (pin "2") (pinfunction "2_2") (pintype "passive"))
    )
    (net (code "153") (name "Net-(Q101-C)") (class "Default")
      (node (ref "LD2") (pin "2") (pintype "passive"))
      (node (ref "Q101") (pin "3") (pinfunction "C_3") (pintype "passive"))
    )
    (net (code "154") (name "VDD_MCU") (class "Default")
      (node (ref "B1") (pin "1") (pinfunction "1_1") (pintype "passive"))
      (node (ref "B1") (pin "2") (pinfunction "2_2") (pintype "passive"))
    )
  )
)
